# bp_to_avr.net
KiCad netlist of a schematic drawn in EAGLE
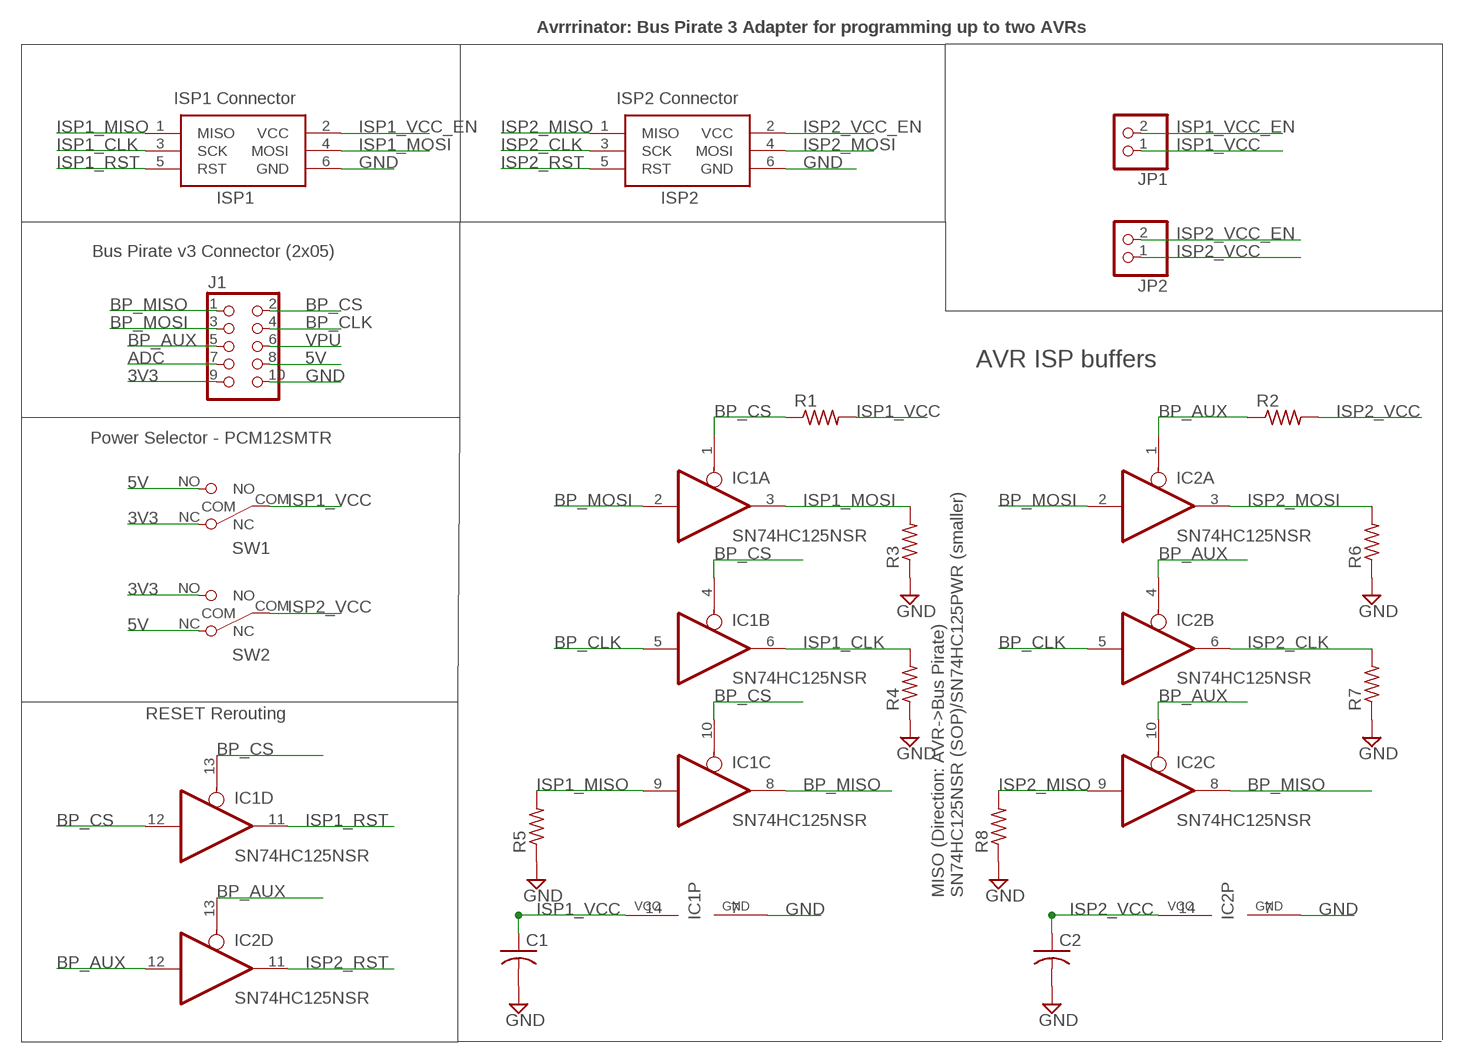
[diagram p0: schematic, sheet 1]

(export (version "E")
  (design (tool "Eeschema 10.0.6"))
  (components
    (comp (ref "C1")
      (value "C-USC0603")
      (footprint "eagle-import:C0603")
      (libsource (lib "eagle-import") (part "C-USC0603"))
    )
    (comp (ref "C2")
      (value "C-USC0603")
      (footprint "eagle-import:C0603")
      (libsource (lib "eagle-import") (part "C-USC0603"))
    )
    (comp (ref "IC1")
      (value "SN74HC125NSR")
      (footprint "eagle-import:AVRRRINATOR-PWR")
      (libsource (lib "eagle-import") (part "AVRRRINATOR_74125PWR"))
    )
    (comp (ref "IC2")
      (value "SN74HC125NSR")
      (footprint "eagle-import:AVRRRINATOR-PWR")
      (libsource (lib "eagle-import") (part "AVRRRINATOR_74125PWR"))
    )
    (comp (ref "ISP1")
      (value "AVRRRINATOR-AVRISP-6PIN-6")
      (footprint "eagle-import:AVRRRINATOR-AVRISP-6PIN")
      (libsource (lib "eagle-import") (part "AVRRRINATOR-AVRISP-6PIN-6"))
    )
    (comp (ref "ISP2")
      (value "AVRRRINATOR-AVRISP-6PIN-6")
      (footprint "eagle-import:AVRRRINATOR-AVRISP-6PIN")
      (libsource (lib "eagle-import") (part "AVRRRINATOR-AVRISP-6PIN-6"))
    )
    (comp (ref "J1")
      (value "CON_HEADER_2X05-PTH+SHROUDED_B")
      (footprint "eagle-import:PINSHRD_PTH_2X05B")
      (libsource (lib "eagle-import") (part "CON_HEADER_2X05-PTH+SHROUDED_B"))
    )
    (comp (ref "JP1")
      (value "HEADER-1X2ROUND")
      (footprint "eagle-import:1X02_ROUND")
      (libsource (lib "eagle-import") (part "HEADER-1X2ROUND"))
    )
    (comp (ref "JP2")
      (value "HEADER-1X2ROUND")
      (footprint "eagle-import:1X02_ROUND")
      (libsource (lib "eagle-import") (part "HEADER-1X2ROUND"))
    )
    (comp (ref "R1")
      (value "R-US_R0603")
      (footprint "eagle-import:R0603")
      (libsource (lib "eagle-import") (part "R-US_R0603"))
    )
    (comp (ref "R2")
      (value "R-US_R0603")
      (footprint "eagle-import:R0603")
      (libsource (lib "eagle-import") (part "R-US_R0603"))
    )
    (comp (ref "R3")
      (value "R-US_R0603")
      (footprint "eagle-import:R0603")
      (libsource (lib "eagle-import") (part "R-US_R0603"))
    )
    (comp (ref "R4")
      (value "R-US_R0603")
      (footprint "eagle-import:R0603")
      (libsource (lib "eagle-import") (part "R-US_R0603"))
    )
    (comp (ref "R5")
      (value "R-US_R0603")
      (footprint "eagle-import:R0603")
      (libsource (lib "eagle-import") (part "R-US_R0603"))
    )
    (comp (ref "R6")
      (value "R-US_R0603")
      (footprint "eagle-import:R0603")
      (libsource (lib "eagle-import") (part "R-US_R0603"))
    )
    (comp (ref "R7")
      (value "R-US_R0603")
      (footprint "eagle-import:R0603")
      (libsource (lib "eagle-import") (part "R-US_R0603"))
    )
    (comp (ref "R8")
      (value "R-US_R0603")
      (footprint "eagle-import:R0603")
      (libsource (lib "eagle-import") (part "R-US_R0603"))
    )
    (comp (ref "SW1")
      (value "SW_SLIDE")
      (footprint "eagle-import:SLIDE_SWITCH_SMD")
      (libsource (lib "eagle-import") (part "SW_SLIDE"))
    )
    (comp (ref "SW2")
      (value "SW_SLIDE")
      (footprint "eagle-import:SLIDE_SWITCH_SMD")
      (libsource (lib "eagle-import") (part "SW_SLIDE"))
    )
  )
  (nets
    (net (code "1") (name "/3V3") (class "Default")
      (node (ref "J1") (pin "9") (pinfunction "9_9") (pintype "passive"))
      (node (ref "SW1") (pin "NC") (pinfunction "NC_NC") (pintype "passive"))
      (node (ref "SW2") (pin "NO") (pinfunction "NO_NO") (pintype "passive"))
    )
    (net (code "2") (name "/5V") (class "Default")
      (node (ref "J1") (pin "8") (pinfunction "8_8") (pintype "passive"))
      (node (ref "SW1") (pin "NO") (pinfunction "NO_NO") (pintype "passive"))
      (node (ref "SW2") (pin "NC") (pinfunction "NC_NC") (pintype "passive"))
    )
    (net (code "3") (name "/ADC") (class "Default")
      (node (ref "J1") (pin "7") (pinfunction "7_7") (pintype "passive"))
    )
    (net (code "4") (name "/BP_AUX") (class "Default")
      (node (ref "IC2") (pin "1") (pinfunction "OE_1") (pintype "input"))
      (node (ref "IC2") (pin "10") (pinfunction "OE_10") (pintype "input"))
      (node (ref "IC2") (pin "12") (pinfunction "I_12") (pintype "input"))
      (node (ref "IC2") (pin "13") (pinfunction "OE_13") (pintype "input"))
      (node (ref "IC2") (pin "4") (pinfunction "OE_4") (pintype "input"))
      (node (ref "J1") (pin "5") (pinfunction "5_5") (pintype "passive"))
      (node (ref "R2") (pin "1") (pinfunction "1_1") (pintype "passive"))
    )
    (net (code "5") (name "/BP_CLK") (class "Default")
      (node (ref "IC1") (pin "5") (pinfunction "I_5") (pintype "input"))
      (node (ref "IC2") (pin "5") (pinfunction "I_5") (pintype "input"))
      (node (ref "J1") (pin "4") (pinfunction "4_4") (pintype "passive"))
    )
    (net (code "6") (name "/BP_CS") (class "Default")
      (node (ref "IC1") (pin "1") (pinfunction "OE_1") (pintype "input"))
      (node (ref "IC1") (pin "10") (pinfunction "OE_10") (pintype "input"))
      (node (ref "IC1") (pin "12") (pinfunction "I_12") (pintype "input"))
      (node (ref "IC1") (pin "13") (pinfunction "OE_13") (pintype "input"))
      (node (ref "IC1") (pin "4") (pinfunction "OE_4") (pintype "input"))
      (node (ref "J1") (pin "2") (pinfunction "2_2") (pintype "passive"))
      (node (ref "R1") (pin "1") (pinfunction "1_1") (pintype "passive"))
    )
    (net (code "7") (name "/BP_MISO") (class "Default")
      (node (ref "IC1") (pin "8") (pinfunction "O_8") (pintype "tri_state"))
      (node (ref "IC2") (pin "8") (pinfunction "O_8") (pintype "tri_state"))
      (node (ref "J1") (pin "1") (pinfunction "1_1") (pintype "passive"))
    )
    (net (code "8") (name "/BP_MOSI") (class "Default")
      (node (ref "IC1") (pin "2") (pinfunction "I_2") (pintype "input"))
      (node (ref "IC2") (pin "2") (pinfunction "I_2") (pintype "input"))
      (node (ref "J1") (pin "3") (pinfunction "3_3") (pintype "passive"))
    )
    (net (code "9") (name "/ISP1_CLK") (class "Default")
      (node (ref "IC1") (pin "6") (pinfunction "O_6") (pintype "tri_state"))
      (node (ref "ISP1") (pin "3") (pinfunction "SCK_3") (pintype "output"))
      (node (ref "R4") (pin "2") (pinfunction "2_2") (pintype "passive"))
    )
    (net (code "10") (name "/ISP1_MISO") (class "Default")
      (node (ref "IC1") (pin "9") (pinfunction "I_9") (pintype "input"))
      (node (ref "ISP1") (pin "1") (pinfunction "MISO_1") (pintype "input"))
      (node (ref "R5") (pin "2") (pinfunction "2_2") (pintype "passive"))
    )
    (net (code "11") (name "/ISP1_MOSI") (class "Default")
      (node (ref "IC1") (pin "3") (pinfunction "O_3") (pintype "tri_state"))
      (node (ref "ISP1") (pin "4") (pinfunction "MOSI_4") (pintype "output"))
      (node (ref "R3") (pin "2") (pinfunction "2_2") (pintype "passive"))
    )
    (net (code "12") (name "/ISP1_RST") (class "Default")
      (node (ref "IC1") (pin "11") (pinfunction "O_11") (pintype "tri_state"))
      (node (ref "ISP1") (pin "5") (pinfunction "RST_5") (pintype "output"))
    )
    (net (code "13") (name "/ISP1_VCC") (class "Default")
      (node (ref "C1") (pin "1") (pinfunction "1_1") (pintype "passive"))
      (node (ref "IC1") (pin "14") (pinfunction "VCC_14") (pintype "power_in"))
      (node (ref "JP1") (pin "1") (pinfunction "1_1") (pintype "passive"))
      (node (ref "R1") (pin "2") (pinfunction "2_2") (pintype "passive"))
      (node (ref "SW1") (pin "COM") (pinfunction "COM_COM") (pintype "passive"))
    )
    (net (code "14") (name "/ISP1_VCC_EN") (class "Default")
      (node (ref "ISP1") (pin "2") (pinfunction "VCC_2") (pintype "power_in"))
      (node (ref "JP1") (pin "2") (pinfunction "2_2") (pintype "passive"))
    )
    (net (code "15") (name "/ISP2_CLK") (class "Default")
      (node (ref "IC2") (pin "6") (pinfunction "O_6") (pintype "tri_state"))
      (node (ref "ISP2") (pin "3") (pinfunction "SCK_3") (pintype "output"))
      (node (ref "R7") (pin "2") (pinfunction "2_2") (pintype "passive"))
    )
    (net (code "16") (name "/ISP2_MISO") (class "Default")
      (node (ref "IC2") (pin "9") (pinfunction "I_9") (pintype "input"))
      (node (ref "ISP2") (pin "1") (pinfunction "MISO_1") (pintype "input"))
      (node (ref "R8") (pin "2") (pinfunction "2_2") (pintype "passive"))
    )
    (net (code "17") (name "/ISP2_MOSI") (class "Default")
      (node (ref "IC2") (pin "3") (pinfunction "O_3") (pintype "tri_state"))
      (node (ref "ISP2") (pin "4") (pinfunction "MOSI_4") (pintype "output"))
      (node (ref "R6") (pin "2") (pinfunction "2_2") (pintype "passive"))
    )
    (net (code "18") (name "/ISP2_RST") (class "Default")
      (node (ref "IC2") (pin "11") (pinfunction "O_11") (pintype "tri_state"))
      (node (ref "ISP2") (pin "5") (pinfunction "RST_5") (pintype "output"))
    )
    (net (code "19") (name "/ISP2_VCC") (class "Default")
      (node (ref "C2") (pin "1") (pinfunction "1_1") (pintype "passive"))
      (node (ref "IC2") (pin "14") (pinfunction "VCC_14") (pintype "power_in"))
      (node (ref "JP2") (pin "1") (pinfunction "1_1") (pintype "passive"))
      (node (ref "R2") (pin "2") (pinfunction "2_2") (pintype "passive"))
      (node (ref "SW2") (pin "COM") (pinfunction "COM_COM") (pintype "passive"))
    )
    (net (code "20") (name "/ISP2_VCC_EN") (class "Default")
      (node (ref "ISP2") (pin "2") (pinfunction "VCC_2") (pintype "power_in"))
      (node (ref "JP2") (pin "2") (pinfunction "2_2") (pintype "passive"))
    )
    (net (code "21") (name "/VPU") (class "Default")
      (node (ref "J1") (pin "6") (pinfunction "6_6") (pintype "passive"))
    )
    (net (code "22") (name "GND") (class "Default")
      (node (ref "C1") (pin "2") (pinfunction "2_2") (pintype "passive"))
      (node (ref "C2") (pin "2") (pinfunction "2_2") (pintype "passive"))
      (node (ref "IC1") (pin "7") (pinfunction "GND_7") (pintype "power_in"))
      (node (ref "IC2") (pin "7") (pinfunction "GND_7") (pintype "power_in"))
      (node (ref "ISP1") (pin "6") (pinfunction "GND_6") (pintype "power_in"))
      (node (ref "ISP2") (pin "6") (pinfunction "GND_6") (pintype "power_in"))
      (node (ref "J1") (pin "10") (pinfunction "10_10") (pintype "passive"))
      (node (ref "R3") (pin "1") (pinfunction "1_1") (pintype "passive"))
      (node (ref "R4") (pin "1") (pinfunction "1_1") (pintype "passive"))
      (node (ref "R5") (pin "1") (pinfunction "1_1") (pintype "passive"))
      (node (ref "R6") (pin "1") (pinfunction "1_1") (pintype "passive"))
      (node (ref "R7") (pin "1") (pinfunction "1_1") (pintype "passive"))
      (node (ref "R8") (pin "1") (pinfunction "1_1") (pintype "passive"))
    )
  )
)
